# Crousel-Pogobed-Motherboard-A.net
KiCad netlist of a schematic drawn in EAGLE
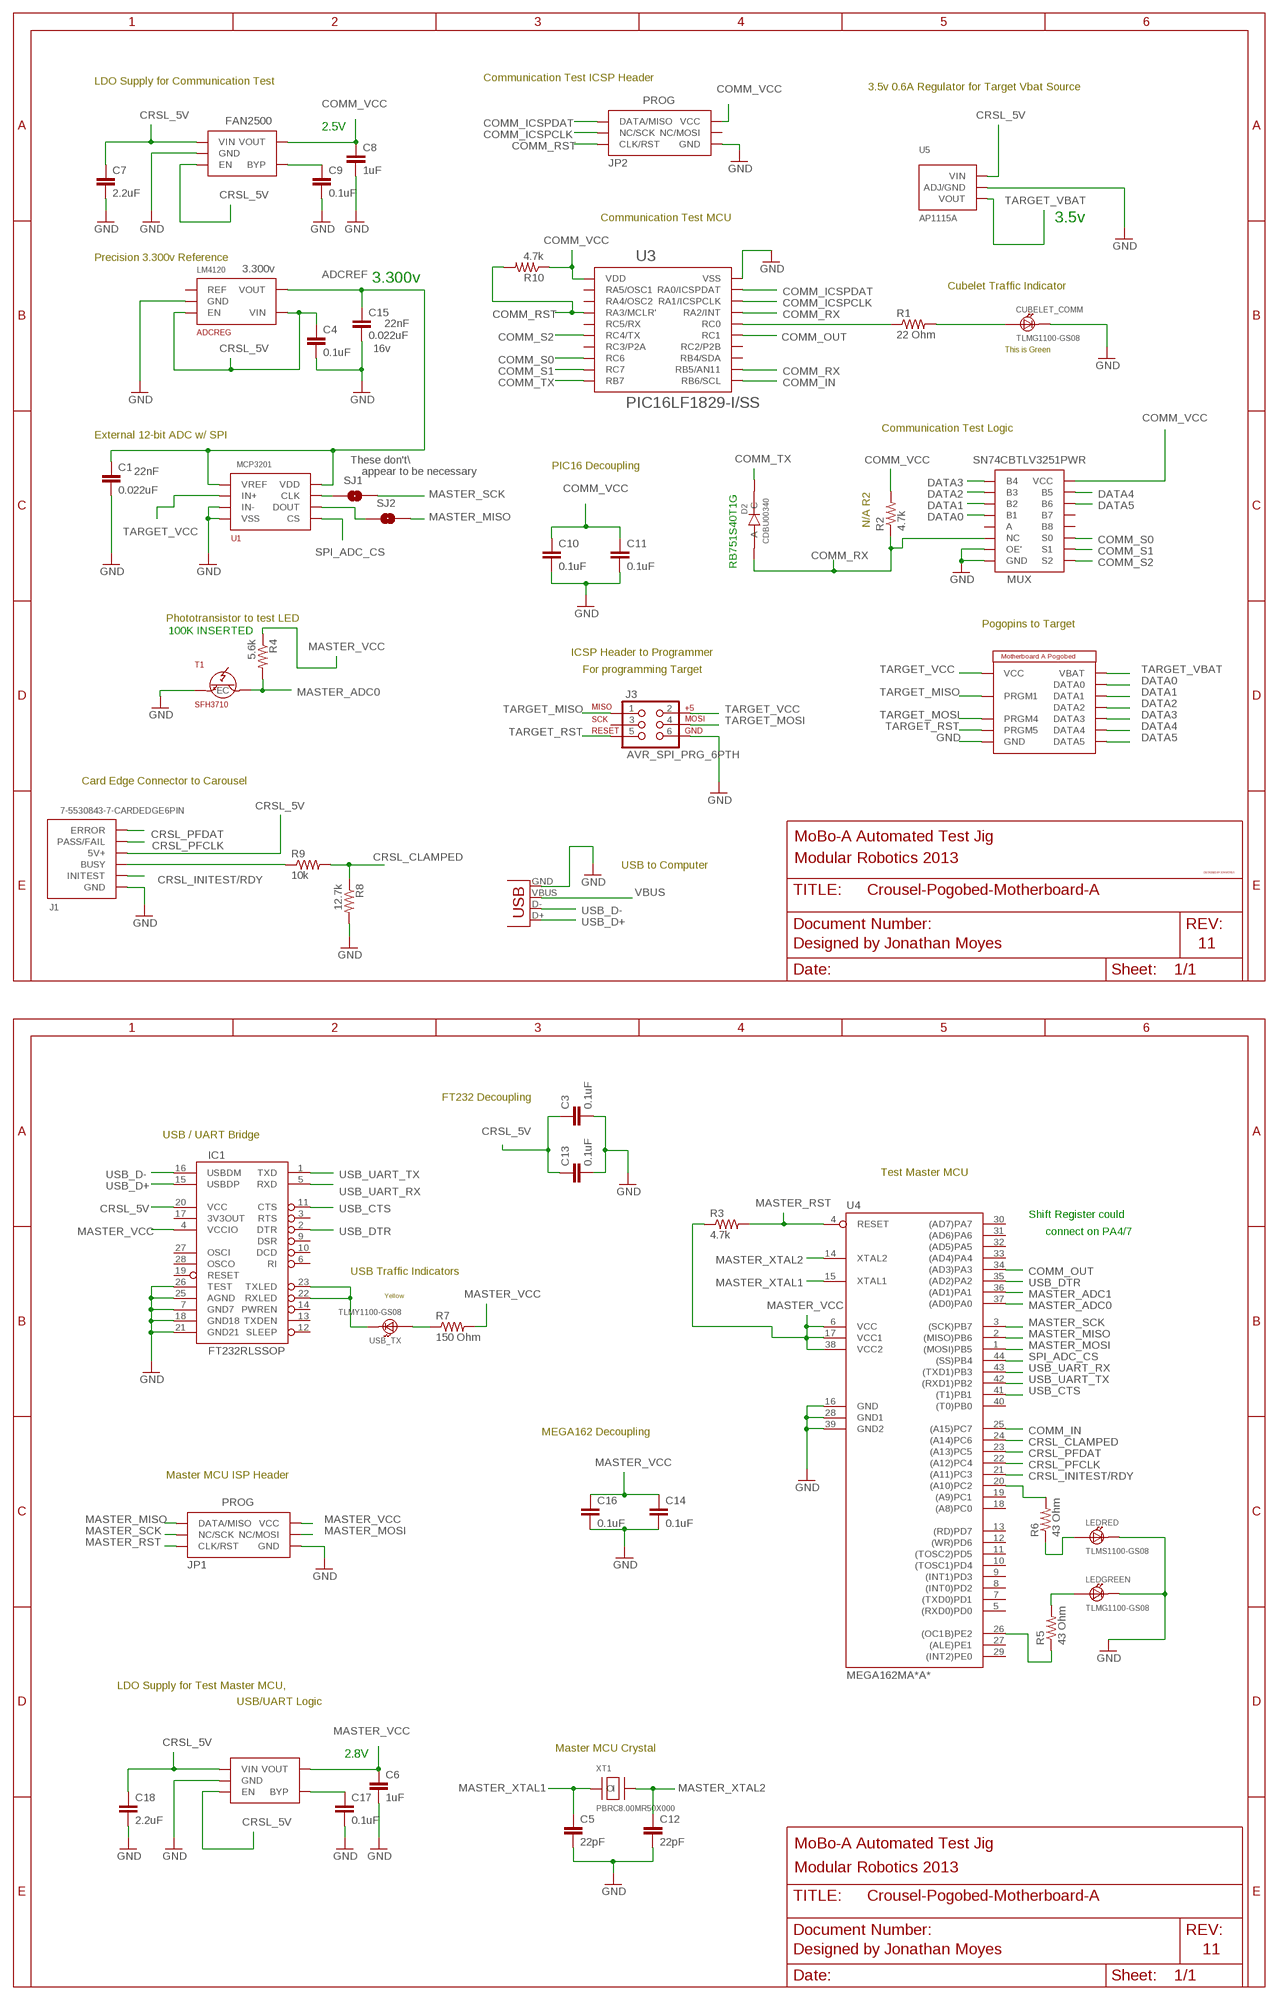
[diagram p0: schematic, sheet 1]

(export (version "E")
  (design (tool "Eeschema 10.0.6"))
  (components
    (comp (ref "2.8V")
      (value "FAN2500")
      (footprint "eagle-import:FAN2500")
      (libsource (lib "eagle-import") (part "FAN2500"))
    )
    (comp (ref "ADCREG")
      (value "LM4120")
      (footprint "eagle-import:LM4120")
      (libsource (lib "eagle-import") (part "LM4120"))
    )
    (comp (ref "C1")
      (value "0.022uF")
      (footprint "eagle-import:0402-CAP")
      (libsource (lib "eagle-import") (part "CAP0402-CAP"))
    )
    (comp (ref "C3")
      (value "0.1uF")
      (footprint "eagle-import:0402-CAP")
      (libsource (lib "eagle-import") (part "CAP0402-CAP"))
    )
    (comp (ref "C4")
      (value "0.1uF")
      (footprint "eagle-import:0402-CAP")
      (libsource (lib "eagle-import") (part "CAP0402-CAP"))
    )
    (comp (ref "C5")
      (value "22pF")
      (footprint "eagle-import:0402-CAP")
      (libsource (lib "eagle-import") (part "CAP0402-CAP"))
    )
    (comp (ref "C6")
      (value "1uF")
      (footprint "eagle-import:0402-CAP")
      (libsource (lib "eagle-import") (part "CAP0402-CAP"))
    )
    (comp (ref "C7")
      (value "2.2uF")
      (footprint "eagle-import:0402-CAP")
      (libsource (lib "eagle-import") (part "CAP0402-CAP"))
    )
    (comp (ref "C8")
      (value "1uF")
      (footprint "eagle-import:0402-CAP")
      (libsource (lib "eagle-import") (part "CAP0402-CAP"))
    )
    (comp (ref "C9")
      (value "0.1uF")
      (footprint "eagle-import:0402-CAP")
      (libsource (lib "eagle-import") (part "CAP0402-CAP"))
    )
    (comp (ref "C10")
      (value "0.1uF")
      (footprint "eagle-import:0402-CAP")
      (libsource (lib "eagle-import") (part "CAP0402-CAP"))
    )
    (comp (ref "C11")
      (value "0.1uF")
      (footprint "eagle-import:0402-CAP")
      (libsource (lib "eagle-import") (part "CAP0402-CAP"))
    )
    (comp (ref "C12")
      (value "22pF")
      (footprint "eagle-import:0402-CAP")
      (libsource (lib "eagle-import") (part "CAP0402-CAP"))
    )
    (comp (ref "C13")
      (value "0.1uF")
      (footprint "eagle-import:0402-CAP")
      (libsource (lib "eagle-import") (part "CAP0402-CAP"))
    )
    (comp (ref "C14")
      (value "0.1uF")
      (footprint "eagle-import:0402-CAP")
      (libsource (lib "eagle-import") (part "CAP0402-CAP"))
    )
    (comp (ref "C15")
      (value "0.022uF")
      (footprint "eagle-import:0402-CAP")
      (libsource (lib "eagle-import") (part "CAP0402-CAP"))
    )
    (comp (ref "C16")
      (value "0.1uF")
      (footprint "eagle-import:0402-CAP")
      (libsource (lib "eagle-import") (part "CAP0402-CAP"))
    )
    (comp (ref "C17")
      (value "0.1uF")
      (footprint "eagle-import:0402-CAP")
      (libsource (lib "eagle-import") (part "CAP0402-CAP"))
    )
    (comp (ref "C18")
      (value "2.2uF")
      (footprint "eagle-import:0402-CAP")
      (libsource (lib "eagle-import") (part "CAP0402-CAP"))
    )
    (comp (ref "COMMREG")
      (value "FAN2500")
      (footprint "eagle-import:FAN2500")
      (libsource (lib "eagle-import") (part "FAN2500"))
    )
    (comp (ref "CUBELET_COMM")
      (value "TLMG1100-GS08")
      (footprint "eagle-import:TLM_1100-GS08")
      (libsource (lib "eagle-import") (part "TLMG1100-GS08"))
    )
    (comp (ref "D2")
      (value "CDBU00340")
      (footprint "eagle-import:CDBU00340")
      (libsource (lib "eagle-import") (part "CDBU00340"))
    )
    (comp (ref "IC1")
      (value "FT232RLSSOP")
      (footprint "eagle-import:SSOP28DB")
      (libsource (lib "eagle-import") (part "FT232RLSSOP"))
    )
    (comp (ref "J1")
      (value "7-5530843-7-CARDEDGE6PIN")
      (footprint "eagle-import:7-5530843-7-CARDEDGE6PIN")
      (libsource (lib "eagle-import") (part "7-5530843-7-CARDEDGE6PIN"))
    )
    (comp (ref "J2")
      (value "MOBOA")
      (footprint "eagle-import:MOBOA")
      (libsource (lib "eagle-import") (part "MOBOA"))
    )
    (comp (ref "J3")
      (value "AVR_SPI_PRG_6PTH")
      (footprint "eagle-import:2X3")
      (libsource (lib "eagle-import") (part "AVR_SPI_PRG_6PTH"))
    )
    (comp (ref "JP1")
      (value "PROG")
      (footprint "eagle-import:PROG")
      (libsource (lib "eagle-import") (part "PROG"))
    )
    (comp (ref "JP2")
      (value "PROG")
      (footprint "eagle-import:PROG")
      (libsource (lib "eagle-import") (part "PROG"))
    )
    (comp (ref "LEDGREEN")
      (value "TLMG1100-GS08")
      (footprint "eagle-import:TLM_1100-GS08")
      (libsource (lib "eagle-import") (part "TLMG1100-GS08"))
    )
    (comp (ref "LEDRED")
      (value "TLMS1100-GS08")
      (footprint "eagle-import:TLM_1100-GS08")
      (libsource (lib "eagle-import") (part "TLMS1100-GS08"))
    )
    (comp (ref "MUX")
      (value "SN74CBTLV3251PWR")
      (footprint "eagle-import:SN74CBTLV3251PWR")
      (libsource (lib "eagle-import") (part "SN74CBTLV3251PWR"))
    )
    (comp (ref "R1")
      (value "22 Ohm")
      (footprint "eagle-import:0402-RES")
      (libsource (lib "eagle-import") (part "RESISTOR0402-RES"))
    )
    (comp (ref "R2")
      (value "4.7k")
      (footprint "eagle-import:0402-RES")
      (libsource (lib "eagle-import") (part "RESISTOR0402-RES"))
    )
    (comp (ref "R3")
      (value "4.7k")
      (footprint "eagle-import:0402-RES")
      (libsource (lib "eagle-import") (part "RESISTOR0402-RES"))
    )
    (comp (ref "R4")
      (value "5.6k")
      (footprint "eagle-import:0402-RES")
      (libsource (lib "eagle-import") (part "RESISTOR0402-RES"))
    )
    (comp (ref "R5")
      (value "43 Ohm")
      (footprint "eagle-import:0402-RES")
      (libsource (lib "eagle-import") (part "RESISTOR0402-RES"))
    )
    (comp (ref "R6")
      (value "43 Ohm")
      (footprint "eagle-import:0402-RES")
      (libsource (lib "eagle-import") (part "RESISTOR0402-RES"))
    )
    (comp (ref "R7")
      (value "150 Ohm")
      (footprint "eagle-import:0402-RES")
      (libsource (lib "eagle-import") (part "RESISTOR0402-RES"))
    )
    (comp (ref "R8")
      (value "12.7k")
      (footprint "eagle-import:0402-RES")
      (libsource (lib "eagle-import") (part "RESISTOR0402-RES"))
    )
    (comp (ref "R9")
      (value "10k")
      (footprint "eagle-import:0402-RES")
      (libsource (lib "eagle-import") (part "RESISTOR0402-RES"))
    )
    (comp (ref "R10")
      (value "4.7k")
      (footprint "eagle-import:0402-RES")
      (libsource (lib "eagle-import") (part "RESISTOR0402-RES"))
    )
    (comp (ref "SJ1")
      (value "SOLDERJUMPERNO")
      (footprint "eagle-import:SJ_2S-NO")
      (libsource (lib "eagle-import") (part "SOLDERJUMPERNO"))
    )
    (comp (ref "SJ2")
      (value "SOLDERJUMPERNO")
      (footprint "eagle-import:SJ_2S-NO")
      (libsource (lib "eagle-import") (part "SOLDERJUMPERNO"))
    )
    (comp (ref "T1")
      (value "SFH3710")
      (footprint "eagle-import:SFH3710")
      (libsource (lib "eagle-import") (part "SFH3710"))
    )
    (comp (ref "U$1")
      (value "JON_MOYES_SIGNATURE")
      (footprint "eagle-import:JON_MOYES_SIGNATURE")
      (libsource (lib "eagle-import") (part "JON_MOYES_SIGNATURE"))
    )
    (comp (ref "U1")
      (value "MCP3201")
      (footprint "eagle-import:MCP3201")
      (libsource (lib "eagle-import") (part "MCP3201"))
    )
    (comp (ref "U3")
      (value "PIC16LF1829-I/SS")
      (footprint "eagle-import:PIC16LF1829-I_SS")
      (libsource (lib "eagle-import") (part "PIC16LF1829-I/SS"))
    )
    (comp (ref "U4")
      (value "MEGA162MA*A*")
      (footprint "eagle-import:TQFP44")
      (libsource (lib "eagle-import") (part "MEGA162MAA"))
    )
    (comp (ref "U5")
      (value "AP1115A")
      (footprint "eagle-import:SOT89")
      (libsource (lib "eagle-import") (part "AP1115A"))
    )
    (comp (ref "USB_TX")
      (value "TLMY1100-GS08")
      (footprint "eagle-import:TLM_1100-GS08")
      (libsource (lib "eagle-import") (part "TLMY1100-GS08"))
    )
    (comp (ref "X1")
      (value "USBPTH")
      (footprint "eagle-import:USB-B-PTH")
      (libsource (lib "eagle-import") (part "USBPTH"))
    )
    (comp (ref "XT1")
      (value "PBRC8.00MR50X000")
      (footprint "eagle-import:PBRC8.00MR50X000")
      (libsource (lib "eagle-import") (part "PBRC8.00MR50X000"))
    )
  )
  (nets
    (net (code "1") (name "/ADCREF") (class "Default")
      (node (ref "ADCREG") (pin "P$5") (pinfunction "VOUT_P$5") (pintype "bidirectional"))
      (node (ref "C1") (pin "1") (pinfunction "1_1") (pintype "passive"))
      (node (ref "C15") (pin "1") (pinfunction "1_1") (pintype "passive"))
      (node (ref "U1") (pin "P$1") (pinfunction "VREF_P$1") (pintype "bidirectional"))
      (node (ref "U1") (pin "P$8") (pinfunction "VDD_P$8") (pintype "bidirectional"))
    )
    (net (code "2") (name "/COMM_ICSPCLK") (class "Default")
      (node (ref "JP2") (pin "P$3") (pinfunction "NC/SCK_P$3") (pintype "bidirectional"))
      (node (ref "U3") (pin "P$18") (pinfunction "RA1/ICSPCLK_P$18") (pintype "bidirectional"))
    )
    (net (code "3") (name "/COMM_ICSPDAT") (class "Default")
      (node (ref "JP2") (pin "P$1") (pinfunction "DATA/MISO_P$1") (pintype "bidirectional"))
      (node (ref "U3") (pin "P$19") (pinfunction "RA0/ICSPDAT_P$19") (pintype "bidirectional"))
    )
    (net (code "4") (name "/COMM_IN") (class "Default")
      (node (ref "U3") (pin "P$11") (pinfunction "RB6/SCL_P$11") (pintype "bidirectional"))
      (node (ref "U4") (pin "25") (pinfunction "(A15)PC7_25") (pintype "bidirectional"))
    )
    (net (code "5") (name "/COMM_OUT") (class "Default")
      (node (ref "U3") (pin "P$15") (pinfunction "RC1_P$15") (pintype "bidirectional"))
      (node (ref "U4") (pin "34") (pinfunction "(AD3)PA3_34") (pintype "bidirectional"))
    )
    (net (code "6") (name "/COMM_RST") (class "Default")
      (node (ref "JP2") (pin "P$5") (pinfunction "CLK/RST_P$5") (pintype "bidirectional"))
      (node (ref "R10") (pin "2") (pinfunction "2_2") (pintype "passive"))
      (node (ref "U3") (pin "P$4") (pinfunction "RA3/MCLR'_P$4") (pintype "bidirectional"))
    )
    (net (code "7") (name "/COMM_RX") (class "Default")
      (node (ref "D2") (pin "P$2") (pinfunction "A_P$2") (pintype "bidirectional"))
      (node (ref "MUX") (pin "P$6") (pinfunction "NC_P$6") (pintype "bidirectional"))
      (node (ref "R2") (pin "1") (pinfunction "1_1") (pintype "passive"))
      (node (ref "U3") (pin "P$12") (pinfunction "RB5/AN11_P$12") (pintype "bidirectional"))
      (node (ref "U3") (pin "P$17") (pinfunction "RA2/INT_P$17") (pintype "bidirectional"))
    )
    (net (code "8") (name "/COMM_S0") (class "Default")
      (node (ref "MUX") (pin "P$11") (pinfunction "S0_P$11") (pintype "bidirectional"))
      (node (ref "U3") (pin "P$8") (pinfunction "RC6_P$8") (pintype "bidirectional"))
    )
    (net (code "9") (name "/COMM_S1") (class "Default")
      (node (ref "MUX") (pin "P$10") (pinfunction "S1_P$10") (pintype "bidirectional"))
      (node (ref "U3") (pin "P$9") (pinfunction "RC7_P$9") (pintype "bidirectional"))
    )
    (net (code "10") (name "/COMM_S2") (class "Default")
      (node (ref "MUX") (pin "P$9") (pinfunction "S2_P$9") (pintype "bidirectional"))
      (node (ref "U3") (pin "P$6") (pinfunction "RC4/TX_P$6") (pintype "bidirectional"))
    )
    (net (code "11") (name "/COMM_TX") (class "Default")
      (node (ref "D2") (pin "P$1") (pinfunction "C_P$1") (pintype "bidirectional"))
      (node (ref "U3") (pin "P$10") (pinfunction "RB7_P$10") (pintype "bidirectional"))
    )
    (net (code "12") (name "/COMM_VCC") (class "Default")
      (node (ref "C10") (pin "1") (pinfunction "1_1") (pintype "passive"))
      (node (ref "C11") (pin "1") (pinfunction "1_1") (pintype "passive"))
      (node (ref "C8") (pin "1") (pinfunction "1_1") (pintype "passive"))
      (node (ref "COMMREG") (pin "P$5") (pinfunction "VOUT_P$5") (pintype "bidirectional"))
      (node (ref "JP2") (pin "P$2") (pinfunction "VCC_P$2") (pintype "bidirectional"))
      (node (ref "MUX") (pin "P$16") (pinfunction "VCC_P$16") (pintype "bidirectional"))
      (node (ref "R10") (pin "1") (pinfunction "1_1") (pintype "passive"))
      (node (ref "R2") (pin "2") (pinfunction "2_2") (pintype "passive"))
      (node (ref "U3") (pin "P$1") (pinfunction "VDD_P$1") (pintype "bidirectional"))
    )
    (net (code "13") (name "/CRSL_5V") (class "Default")
      (node (ref "2.8V") (pin "P$1") (pinfunction "VIN_P$1") (pintype "bidirectional"))
      (node (ref "2.8V") (pin "P$3") (pinfunction "EN_P$3") (pintype "bidirectional"))
      (node (ref "ADCREG") (pin "P$3") (pinfunction "EN_P$3") (pintype "bidirectional"))
      (node (ref "ADCREG") (pin "P$4") (pinfunction "VIN_P$4") (pintype "bidirectional"))
      (node (ref "C13") (pin "1") (pinfunction "1_1") (pintype "passive"))
      (node (ref "C18") (pin "1") (pinfunction "1_1") (pintype "passive"))
      (node (ref "C3") (pin "1") (pinfunction "1_1") (pintype "passive"))
      (node (ref "C4") (pin "1") (pinfunction "1_1") (pintype "passive"))
      (node (ref "C7") (pin "1") (pinfunction "1_1") (pintype "passive"))
      (node (ref "COMMREG") (pin "P$1") (pinfunction "VIN_P$1") (pintype "bidirectional"))
      (node (ref "COMMREG") (pin "P$3") (pinfunction "EN_P$3") (pintype "bidirectional"))
      (node (ref "IC1") (pin "20") (pinfunction "VCC_20") (pintype "power_in"))
      (node (ref "J1") (pin "P$4") (pinfunction "5V+_P$4") (pintype "bidirectional"))
      (node (ref "U5") (pin "3") (pinfunction "VIN_3") (pintype "bidirectional"))
    )
    (net (code "14") (name "/CRSL_CLAMPED") (class "Default")
      (node (ref "R8") (pin "1") (pinfunction "1_1") (pintype "passive"))
      (node (ref "R9") (pin "2") (pinfunction "2_2") (pintype "passive"))
      (node (ref "U4") (pin "24") (pinfunction "(A14)PC6_24") (pintype "bidirectional"))
    )
    (net (code "15") (name "/CRSL_INITEST{slash}RDY") (class "Default")
      (node (ref "J1") (pin "P$2") (pinfunction "INITEST_P$2") (pintype "bidirectional"))
      (node (ref "U4") (pin "21") (pinfunction "(A11)PC3_21") (pintype "bidirectional"))
    )
    (net (code "16") (name "/CRSL_PFCLK") (class "Default")
      (node (ref "J1") (pin "P$5") (pinfunction "PASS/FAIL_P$5") (pintype "bidirectional"))
      (node (ref "U4") (pin "22") (pinfunction "(A12)PC4_22") (pintype "bidirectional"))
    )
    (net (code "17") (name "/CRSL_PFDAT") (class "Default")
      (node (ref "J1") (pin "P$6") (pinfunction "ERROR_P$6") (pintype "bidirectional"))
      (node (ref "U4") (pin "23") (pinfunction "(A13)PC5_23") (pintype "bidirectional"))
    )
    (net (code "18") (name "/DATA0") (class "Default")
      (node (ref "J2") (pin "DATA0") (pinfunction "DATA0_DATA0") (pintype "bidirectional"))
      (node (ref "MUX") (pin "P$4") (pinfunction "B1_P$4") (pintype "bidirectional"))
    )
    (net (code "19") (name "/DATA1") (class "Default")
      (node (ref "J2") (pin "DATA1") (pinfunction "DATA1_DATA1") (pintype "bidirectional"))
      (node (ref "MUX") (pin "P$3") (pinfunction "B2_P$3") (pintype "bidirectional"))
    )
    (net (code "20") (name "/DATA2") (class "Default")
      (node (ref "J2") (pin "DATA2") (pinfunction "DATA2_DATA2") (pintype "bidirectional"))
      (node (ref "MUX") (pin "P$2") (pinfunction "B3_P$2") (pintype "bidirectional"))
    )
    (net (code "21") (name "/DATA3") (class "Default")
      (node (ref "J2") (pin "DATA3") (pinfunction "DATA3_DATA3") (pintype "bidirectional"))
      (node (ref "MUX") (pin "P$1") (pinfunction "B4_P$1") (pintype "bidirectional"))
    )
    (net (code "22") (name "/DATA4") (class "Default")
      (node (ref "J2") (pin "DATA4") (pinfunction "DATA4_DATA4") (pintype "bidirectional"))
      (node (ref "MUX") (pin "P$15") (pinfunction "B5_P$15") (pintype "bidirectional"))
    )
    (net (code "23") (name "/DATA5") (class "Default")
      (node (ref "J2") (pin "DATA5") (pinfunction "DATA5_DATA5") (pintype "bidirectional"))
      (node (ref "MUX") (pin "P$14") (pinfunction "B6_P$14") (pintype "bidirectional"))
    )
    (net (code "24") (name "/MASTER_ADC0") (class "Default")
      (node (ref "R4") (pin "2") (pinfunction "2_2") (pintype "passive"))
      (node (ref "T1") (pin "C") (pinfunction "C_C") (pintype "bidirectional"))
      (node (ref "U4") (pin "37") (pinfunction "(AD0)PA0_37") (pintype "bidirectional"))
    )
    (net (code "25") (name "/MASTER_ADC1") (class "Default")
      (node (ref "U4") (pin "36") (pinfunction "(AD1)PA1_36") (pintype "bidirectional"))
    )
    (net (code "26") (name "/MASTER_MISO") (class "Default")
      (node (ref "JP1") (pin "P$1") (pinfunction "DATA/MISO_P$1") (pintype "bidirectional"))
      (node (ref "SJ2") (pin "2") (pinfunction "2_2") (pintype "passive"))
      (node (ref "U4") (pin "2") (pinfunction "(MISO)PB6_2") (pintype "bidirectional"))
    )
    (net (code "27") (name "/MASTER_MOSI") (class "Default")
      (node (ref "JP1") (pin "P$4") (pinfunction "NC/MOSI_P$4") (pintype "bidirectional"))
      (node (ref "U4") (pin "1") (pinfunction "(MOSI)PB5_1") (pintype "bidirectional"))
    )
    (net (code "28") (name "/MASTER_RST") (class "Default")
      (node (ref "JP1") (pin "P$5") (pinfunction "CLK/RST_P$5") (pintype "bidirectional"))
      (node (ref "R3") (pin "2") (pinfunction "2_2") (pintype "passive"))
      (node (ref "U4") (pin "4") (pinfunction "RESET_4") (pintype "input"))
    )
    (net (code "29") (name "/MASTER_SCK") (class "Default")
      (node (ref "JP1") (pin "P$3") (pinfunction "NC/SCK_P$3") (pintype "bidirectional"))
      (node (ref "SJ1") (pin "2") (pinfunction "2_2") (pintype "passive"))
      (node (ref "U4") (pin "3") (pinfunction "(SCK)PB7_3") (pintype "bidirectional"))
    )
    (net (code "30") (name "/MASTER_VCC") (class "Default")
      (node (ref "2.8V") (pin "P$5") (pinfunction "VOUT_P$5") (pintype "bidirectional"))
      (node (ref "C14") (pin "1") (pinfunction "1_1") (pintype "passive"))
      (node (ref "C16") (pin "1") (pinfunction "1_1") (pintype "passive"))
      (node (ref "C6") (pin "1") (pinfunction "1_1") (pintype "passive"))
      (node (ref "IC1") (pin "4") (pinfunction "VCCIO_4") (pintype "power_in"))
      (node (ref "JP1") (pin "P$2") (pinfunction "VCC_P$2") (pintype "bidirectional"))
      (node (ref "R3") (pin "1") (pinfunction "1_1") (pintype "passive"))
      (node (ref "R4") (pin "1") (pinfunction "1_1") (pintype "passive"))
      (node (ref "R7") (pin "2") (pinfunction "2_2") (pintype "passive"))
      (node (ref "U4") (pin "17") (pinfunction "VCC1_17") (pintype "power_in"))
      (node (ref "U4") (pin "38") (pinfunction "VCC2_38") (pintype "power_in"))
      (node (ref "U4") (pin "6") (pinfunction "VCC_6") (pintype "power_in"))
    )
    (net (code "31") (name "/MASTER_XTAL1") (class "Default")
      (node (ref "C5") (pin "1") (pinfunction "1_1") (pintype "passive"))
      (node (ref "U4") (pin "15") (pinfunction "XTAL1_15") (pintype "input"))
      (node (ref "XT1") (pin "I") (pinfunction "I_I") (pintype "bidirectional"))
    )
    (net (code "32") (name "/MASTER_XTAL2") (class "Default")
      (node (ref "C12") (pin "1") (pinfunction "1_1") (pintype "passive"))
      (node (ref "U4") (pin "14") (pinfunction "XTAL2_14") (pintype "input"))
      (node (ref "XT1") (pin "O") (pinfunction "O_O") (pintype "bidirectional"))
    )
    (net (code "33") (name "/SPI_ADC_CS") (class "Default")
      (node (ref "U1") (pin "P$5") (pinfunction "CS_P$5") (pintype "bidirectional"))
      (node (ref "U4") (pin "44") (pinfunction "(SS)PB4_44") (pintype "bidirectional"))
    )
    (net (code "34") (name "/TARGET_MISO") (class "Default")
      (node (ref "J2") (pin "PRGM1") (pinfunction "PRGM1_PRGM1") (pintype "bidirectional"))
      (node (ref "J3") (pin "1") (pinfunction "1_1") (pintype "passive"))
    )
    (net (code "35") (name "/TARGET_MOSI") (class "Default")
      (node (ref "J2") (pin "PRGM4") (pinfunction "PRGM4_PRGM4") (pintype "bidirectional"))
      (node (ref "J3") (pin "4") (pinfunction "4_4") (pintype "passive"))
    )
    (net (code "36") (name "/TARGET_RST") (class "Default")
      (node (ref "J2") (pin "PRGM5") (pinfunction "PRGM5_PRGM5") (pintype "bidirectional"))
      (node (ref "J3") (pin "5") (pinfunction "5_5") (pintype "passive"))
    )
    (net (code "37") (name "/TARGET_VBAT") (class "Default")
      (node (ref "J2") (pin "VBAT") (pinfunction "VBAT_VBAT") (pintype "bidirectional"))
      (node (ref "U5") (pin "1") (pinfunction "VOUT_1") (pintype "bidirectional"))
    )
    (net (code "38") (name "/TARGET_VCC") (class "Default")
      (node (ref "J2") (pin "PRGM2/VCC") (pinfunction "VCC_PRGM2/VCC") (pintype "bidirectional"))
      (node (ref "J3") (pin "2") (pinfunction "2_2") (pintype "passive"))
      (node (ref "U1") (pin "P$2") (pinfunction "IN+_P$2") (pintype "bidirectional"))
    )
    (net (code "39") (name "/USB_CTS") (class "Default")
      (node (ref "IC1") (pin "11") (pinfunction "CTS_11") (pintype "input"))
      (node (ref "U4") (pin "41") (pinfunction "(T1)PB1_41") (pintype "bidirectional"))
    )
    (net (code "40") (name "/USB_D+") (class "Default")
      (node (ref "IC1") (pin "15") (pinfunction "USBDP_15") (pintype "bidirectional"))
      (node (ref "X1") (pin "D+") (pinfunction "D+_D+") (pintype "bidirectional"))
    )
    (net (code "41") (name "/USB_D-") (class "Default")
      (node (ref "IC1") (pin "16") (pinfunction "USBDM_16") (pintype "bidirectional"))
      (node (ref "X1") (pin "D-") (pinfunction "D-_D-") (pintype "bidirectional"))
    )
    (net (code "42") (name "/USB_DTR") (class "Default")
      (node (ref "IC1") (pin "2") (pinfunction "DTR_2") (pintype "output"))
      (node (ref "U4") (pin "35") (pinfunction "(AD2)PA2_35") (pintype "bidirectional"))
    )
    (net (code "43") (name "/USB_UART_RX") (class "Default")
      (node (ref "IC1") (pin "5") (pinfunction "RXD_5") (pintype "input"))
      (node (ref "U4") (pin "43") (pinfunction "(TXD1)PB3_43") (pintype "bidirectional"))
    )
    (net (code "44") (name "/USB_UART_TX") (class "Default")
      (node (ref "IC1") (pin "1") (pinfunction "TXD_1") (pintype "output"))
      (node (ref "U4") (pin "42") (pinfunction "(RXD1)PB2_42") (pintype "bidirectional"))
    )
    (net (code "45") (name "/VBUS") (class "Default")
      (node (ref "X1") (pin "VBUS") (pinfunction "VBUS_VBUS") (pintype "bidirectional"))
    )
    (net (code "46") (name "GND") (class "Default")
      (node (ref "2.8V") (pin "P$2") (pinfunction "GND_P$2") (pintype "bidirectional"))
      (node (ref "ADCREG") (pin "P$2") (pinfunction "GND_P$2") (pintype "bidirectional"))
      (node (ref "C1") (pin "2") (pinfunction "2_2") (pintype "passive"))
      (node (ref "C10") (pin "2") (pinfunction "2_2") (pintype "passive"))
      (node (ref "C11") (pin "2") (pinfunction "2_2") (pintype "passive"))
      (node (ref "C12") (pin "2") (pinfunction "2_2") (pintype "passive"))
      (node (ref "C13") (pin "2") (pinfunction "2_2") (pintype "passive"))
      (node (ref "C14") (pin "2") (pinfunction "2_2") (pintype "passive"))
      (node (ref "C15") (pin "2") (pinfunction "2_2") (pintype "passive"))
      (node (ref "C16") (pin "2") (pinfunction "2_2") (pintype "passive"))
      (node (ref "C17") (pin "2") (pinfunction "2_2") (pintype "passive"))
      (node (ref "C18") (pin "2") (pinfunction "2_2") (pintype "passive"))
      (node (ref "C3") (pin "2") (pinfunction "2_2") (pintype "passive"))
      (node (ref "C4") (pin "2") (pinfunction "2_2") (pintype "passive"))
      (node (ref "C5") (pin "2") (pinfunction "2_2") (pintype "passive"))
      (node (ref "C6") (pin "2") (pinfunction "2_2") (pintype "passive"))
      (node (ref "C7") (pin "2") (pinfunction "2_2") (pintype "passive"))
      (node (ref "C8") (pin "2") (pinfunction "2_2") (pintype "passive"))
      (node (ref "C9") (pin "2") (pinfunction "2_2") (pintype "passive"))
      (node (ref "COMMREG") (pin "P$2") (pinfunction "GND_P$2") (pintype "bidirectional"))
      (node (ref "CUBELET_COMM") (pin "C") (pinfunction "C_C") (pintype "bidirectional"))
      (node (ref "IC1") (pin "18") (pinfunction "GND18_18") (pintype "power_in"))
      (node (ref "IC1") (pin "21") (pinfunction "GND21_21") (pintype "power_in"))
      (node (ref "IC1") (pin "25") (pinfunction "AGND_25") (pintype "power_in"))
      (node (ref "IC1") (pin "26") (pinfunction "TEST_26") (pintype "input"))
      (node (ref "IC1") (pin "7") (pinfunction "GND7_7") (pintype "power_in"))
      (node (ref "J1") (pin "P$3") (pinfunction "GND_P$3") (pintype "bidirectional"))
      (node (ref "J2") (pin "PRGM6/GND") (pinfunction "GND_PRGM6/GND") (pintype "bidirectional"))
      (node (ref "J3") (pin "6") (pinfunction "6_6") (pintype "passive"))
      (node (ref "JP1") (pin "P$6") (pinfunction "GND_P$6") (pintype "bidirectional"))
      (node (ref "JP2") (pin "P$6") (pinfunction "GND_P$6") (pintype "bidirectional"))
      (node (ref "LEDGREEN") (pin "C") (pinfunction "C_C") (pintype "bidirectional"))
      (node (ref "LEDRED") (pin "C") (pinfunction "C_C") (pintype "bidirectional"))
      (node (ref "MUX") (pin "P$7") (pinfunction "OE'_P$7") (pintype "bidirectional"))
      (node (ref "MUX") (pin "P$8") (pinfunction "GND_P$8") (pintype "bidirectional"))
      (node (ref "R8") (pin "2") (pinfunction "2_2") (pintype "passive"))
      (node (ref "T1") (pin "E") (pinfunction "E_E") (pintype "bidirectional"))
      (node (ref "U1") (pin "P$3") (pinfunction "IN-_P$3") (pintype "bidirectional"))
      (node (ref "U1") (pin "P$4") (pinfunction "VSS_P$4") (pintype "bidirectional"))
      (node (ref "U3") (pin "P$20") (pinfunction "VSS_P$20") (pintype "bidirectional"))
      (node (ref "U4") (pin "16") (pinfunction "GND_16") (pintype "power_in"))
      (node (ref "U4") (pin "28") (pinfunction "GND1_28") (pintype "power_in"))
      (node (ref "U4") (pin "39") (pinfunction "GND2_39") (pintype "power_in"))
      (node (ref "U5") (pin "2") (pinfunction "ADJ/GND_2") (pintype "bidirectional"))
      (node (ref "U5") (pin "2@1") (pinfunction "ADJ/GND_2@1") (pintype "bidirectional"))
      (node (ref "X1") (pin "GND") (pinfunction "GND_GND") (pintype "bidirectional"))
    )
    (net (code "47") (name "Net-(2.8V-BYP)") (class "Default")
      (node (ref "2.8V") (pin "P$4") (pinfunction "BYP_P$4") (pintype "bidirectional"))
      (node (ref "C17") (pin "1") (pinfunction "1_1") (pintype "passive"))
    )
    (net (code "48") (name "Net-(COMMREG-BYP)") (class "Default")
      (node (ref "C9") (pin "1") (pinfunction "1_1") (pintype "passive"))
      (node (ref "COMMREG") (pin "P$4") (pinfunction "BYP_P$4") (pintype "bidirectional"))
    )
    (net (code "49") (name "Net-(CUBELET_COMM-PadA)") (class "Default")
      (node (ref "CUBELET_COMM") (pin "A") (pinfunction "A_A") (pintype "bidirectional"))
      (node (ref "R1") (pin "2") (pinfunction "2_2") (pintype "passive"))
    )
    (net (code "50") (name "Net-(IC1-RXLED)") (class "Default")
      (node (ref "IC1") (pin "22") (pinfunction "RXLED_22") (pintype "input"))
      (node (ref "IC1") (pin "23") (pinfunction "TXLED_23") (pintype "input"))
      (node (ref "USB_TX") (pin "C") (pinfunction "C_C") (pintype "bidirectional"))
    )
    (net (code "51") (name "Net-(J1-BUSY)") (class "Default")
      (node (ref "J1") (pin "P$1") (pinfunction "BUSY_P$1") (pintype "bidirectional"))
      (node (ref "R9") (pin "1") (pinfunction "1_1") (pintype "passive"))
    )
    (net (code "52") (name "Net-(LEDGREEN-PadA)") (class "Default")
      (node (ref "LEDGREEN") (pin "A") (pinfunction "A_A") (pintype "bidirectional"))
      (node (ref "R5") (pin "2") (pinfunction "2_2") (pintype "passive"))
    )
    (net (code "53") (name "Net-(LEDRED-PadA)") (class "Default")
      (node (ref "LEDRED") (pin "A") (pinfunction "A_A") (pintype "bidirectional"))
      (node (ref "R6") (pin "1") (pinfunction "1_1") (pintype "passive"))
    )
    (net (code "54") (name "Net-(R7-Pad1)") (class "Default")
      (node (ref "R7") (pin "1") (pinfunction "1_1") (pintype "passive"))
      (node (ref "USB_TX") (pin "A") (pinfunction "A_A") (pintype "bidirectional"))
    )
    (net (code "55") (name "Net-(U1-CLK)") (class "Default")
      (node (ref "SJ1") (pin "1") (pinfunction "1_1") (pintype "passive"))
      (node (ref "U1") (pin "P$7") (pinfunction "CLK_P$7") (pintype "bidirectional"))
    )
    (net (code "56") (name "Net-(U1-DOUT)") (class "Default")
      (node (ref "SJ2") (pin "1") (pinfunction "1_1") (pintype "passive"))
      (node (ref "U1") (pin "P$6") (pinfunction "DOUT_P$6") (pintype "bidirectional"))
    )
    (net (code "57") (name "Net-(U3-RC0)") (class "Default")
      (node (ref "R1") (pin "1") (pinfunction "1_1") (pintype "passive"))
      (node (ref "U3") (pin "P$16") (pinfunction "RC0_P$16") (pintype "bidirectional"))
    )
    (net (code "58") (name "Net-(U4-(A10)PC2)") (class "Default")
      (node (ref "R6") (pin "2") (pinfunction "2_2") (pintype "passive"))
      (node (ref "U4") (pin "20") (pinfunction "(A10)PC2_20") (pintype "bidirectional"))
    )
    (net (code "59") (name "Net-(U4-(OC1B)PE2)") (class "Default")
      (node (ref "R5") (pin "1") (pinfunction "1_1") (pintype "passive"))
      (node (ref "U4") (pin "26") (pinfunction "(OC1B)PE2_26") (pintype "bidirectional"))
    )
    (net (code "60") (name "unconnected-(ADCREG-REF-PadP$1)") (class "Default")
      (node (ref "ADCREG") (pin "P$1") (pinfunction "REF_P$1") (pintype "bidirectional"))
    )
    (net (code "61") (name "unconnected-(IC1-3V3OUT-Pad17)") (class "Default")
      (node (ref "IC1") (pin "17") (pinfunction "3V3OUT_17") (pintype "output"))
    )
    (net (code "62") (name "unconnected-(IC1-DCD-Pad10)") (class "Default")
      (node (ref "IC1") (pin "10") (pinfunction "DCD_10") (pintype "input"))
    )
    (net (code "63") (name "unconnected-(IC1-DSR-Pad9)") (class "Default")
      (node (ref "IC1") (pin "9") (pinfunction "DSR_9") (pintype "input"))
    )
    (net (code "64") (name "unconnected-(IC1-OSCI-Pad27)") (class "Default")
      (node (ref "IC1") (pin "27") (pinfunction "OSCI_27") (pintype "input"))
    )
    (net (code "65") (name "unconnected-(IC1-OSCO-Pad28)") (class "Default")
      (node (ref "IC1") (pin "28") (pinfunction "OSCO_28") (pintype "output"))
    )
    (net (code "66") (name "unconnected-(IC1-PWREN-Pad14)") (class "Default")
      (node (ref "IC1") (pin "14") (pinfunction "PWREN_14") (pintype "input"))
    )
    (net (code "67") (name "unconnected-(IC1-RESET-Pad19)") (class "Default")
      (node (ref "IC1") (pin "19") (pinfunction "RESET_19") (pintype "input"))
    )
    (net (code "68") (name "unconnected-(IC1-RI-Pad6)") (class "Default")
      (node (ref "IC1") (pin "6") (pinfunction "RI_6") (pintype "input"))
    )
    (net (code "69") (name "unconnected-(IC1-RTS-Pad3)") (class "Default")
      (node (ref "IC1") (pin "3") (pinfunction "RTS_3") (pintype "output"))
    )
    (net (code "70") (name "unconnected-(IC1-SLEEP-Pad12)") (class "Default")
      (node (ref "IC1") (pin "12") (pinfunction "SLEEP_12") (pintype "input"))
    )
    (net (code "71") (name "unconnected-(IC1-TXDEN-Pad13)") (class "Default")
      (node (ref "IC1") (pin "13") (pinfunction "TXDEN_13") (pintype "input"))
    )
    (net (code "72") (name "unconnected-(J3-Pad3)") (class "Default")
      (node (ref "J3") (pin "3") (pinfunction "3_3") (pintype "passive"))
    )
    (net (code "73") (name "unconnected-(JP2-NC{slash}MOSI-PadP$4)") (class "Default")
      (node (ref "JP2") (pin "P$4") (pinfunction "NC/MOSI_P$4") (pintype "bidirectional"))
    )
    (net (code "74") (name "unconnected-(MUX-A-PadP$5)") (class "Default")
      (node (ref "MUX") (pin "P$5") (pinfunction "A_P$5") (pintype "bidirectional"))
    )
    (net (code "75") (name "unconnected-(MUX-B7-PadP$13)") (class "Default")
      (node (ref "MUX") (pin "P$13") (pinfunction "B7_P$13") (pintype "bidirectional"))
    )
    (net (code "76") (name "unconnected-(MUX-B8-PadP$12)") (class "Default")
      (node (ref "MUX") (pin "P$12") (pinfunction "B8_P$12") (pintype "bidirectional"))
    )
    (net (code "77") (name "unconnected-(U3-RA4{slash}OSC2-PadP$3)") (class "Default")
      (node (ref "U3") (pin "P$3") (pinfunction "RA4/OSC2_P$3") (pintype "bidirectional"))
    )
    (net (code "78") (name "unconnected-(U3-RA5{slash}OSC1-PadP$2)") (class "Default")
      (node (ref "U3") (pin "P$2") (pinfunction "RA5/OSC1_P$2") (pintype "bidirectional"))
    )
    (net (code "79") (name "unconnected-(U3-RB4{slash}SDA-PadP$13)") (class "Default")
      (node (ref "U3") (pin "P$13") (pinfunction "RB4/SDA_P$13") (pintype "bidirectional"))
    )
    (net (code "80") (name "unconnected-(U3-RC2{slash}P2B-PadP$14)") (class "Default")
      (node (ref "U3") (pin "P$14") (pinfunction "RC2/P2B_P$14") (pintype "bidirectional"))
    )
    (net (code "81") (name "unconnected-(U3-RC3{slash}P2A-PadP$7)") (class "Default")
      (node (ref "U3") (pin "P$7") (pinfunction "RC3/P2A_P$7") (pintype "bidirectional"))
    )
    (net (code "82") (name "unconnected-(U3-RC5{slash}RX-PadP$5)") (class "Default")
      (node (ref "U3") (pin "P$5") (pinfunction "RC5/RX_P$5") (pintype "bidirectional"))
    )
    (net (code "83") (name "unconnected-(U4-(A8)PC0-Pad18)") (class "Default")
      (node (ref "U4") (pin "18") (pinfunction "(A8)PC0_18") (pintype "bidirectional"))
    )
    (net (code "84") (name "unconnected-(U4-(A9)PC1-Pad19)") (class "Default")
      (node (ref "U4") (pin "19") (pinfunction "(A9)PC1_19") (pintype "bidirectional"))
    )
    (net (code "85") (name "unconnected-(U4-(AD4)PA4-Pad33)") (class "Default")
      (node (ref "U4") (pin "33") (pinfunction "(AD4)PA4_33") (pintype "bidirectional"))
    )
    (net (code "86") (name "unconnected-(U4-(AD5)PA5-Pad32)") (class "Default")
      (node (ref "U4") (pin "32") (pinfunction "(AD5)PA5_32") (pintype "bidirectional"))
    )
    (net (code "87") (name "unconnected-(U4-(AD6)PA6-Pad31)") (class "Default")
      (node (ref "U4") (pin "31") (pinfunction "(AD6)PA6_31") (pintype "bidirectional"))
    )
    (net (code "88") (name "unconnected-(U4-(AD7)PA7-Pad30)") (class "Default")
      (node (ref "U4") (pin "30") (pinfunction "(AD7)PA7_30") (pintype "bidirectional"))
    )
    (net (code "89") (name "unconnected-(U4-(ALE)PE1-Pad27)") (class "Default")
      (node (ref "U4") (pin "27") (pinfunction "(ALE)PE1_27") (pintype "bidirectional"))
    )
    (net (code "90") (name "unconnected-(U4-(INT0)PD2-Pad8)") (class "Default")
      (node (ref "U4") (pin "8") (pinfunction "(INT0)PD2_8") (pintype "bidirectional"))
    )
    (net (code "91") (name "unconnected-(U4-(INT1)PD3-Pad9)") (class "Default")
      (node (ref "U4") (pin "9") (pinfunction "(INT1)PD3_9") (pintype "bidirectional"))
    )
    (net (code "92") (name "unconnected-(U4-(INT2)PE0-Pad29)") (class "Default")
      (node (ref "U4") (pin "29") (pinfunction "(INT2)PE0_29") (pintype "bidirectional"))
    )
    (net (code "93") (name "unconnected-(U4-(RD)PD7-Pad13)") (class "Default")
      (node (ref "U4") (pin "13") (pinfunction "(RD)PD7_13") (pintype "bidirectional"))
    )
    (net (code "94") (name "unconnected-(U4-(RXD0)PD0-Pad5)") (class "Default")
      (node (ref "U4") (pin "5") (pinfunction "(RXD0)PD0_5") (pintype "bidirectional"))
    )
    (net (code "95") (name "unconnected-(U4-(T0)PB0-Pad40)") (class "Default")
      (node (ref "U4") (pin "40") (pinfunction "(T0)PB0_40") (pintype "bidirectional"))
    )
    (net (code "96") (name "unconnected-(U4-(TOSC1)PD4-Pad10)") (class "Default")
      (node (ref "U4") (pin "10") (pinfunction "(TOSC1)PD4_10") (pintype "bidirectional"))
    )
    (net (code "97") (name "unconnected-(U4-(TOSC2)PD5-Pad11)") (class "Default")
      (node (ref "U4") (pin "11") (pinfunction "(TOSC2)PD5_11") (pintype "bidirectional"))
    )
    (net (code "98") (name "unconnected-(U4-(TXD0)PD1-Pad7)") (class "Default")
      (node (ref "U4") (pin "7") (pinfunction "(TXD0)PD1_7") (pintype "bidirectional"))
    )
    (net (code "99") (name "unconnected-(U4-(WR)PD6-Pad12)") (class "Default")
      (node (ref "U4") (pin "12") (pinfunction "(WR)PD6_12") (pintype "bidirectional"))
    )
  )
)
